# Untitled.net
KiCad netlist of a schematic drawn in EAGLE
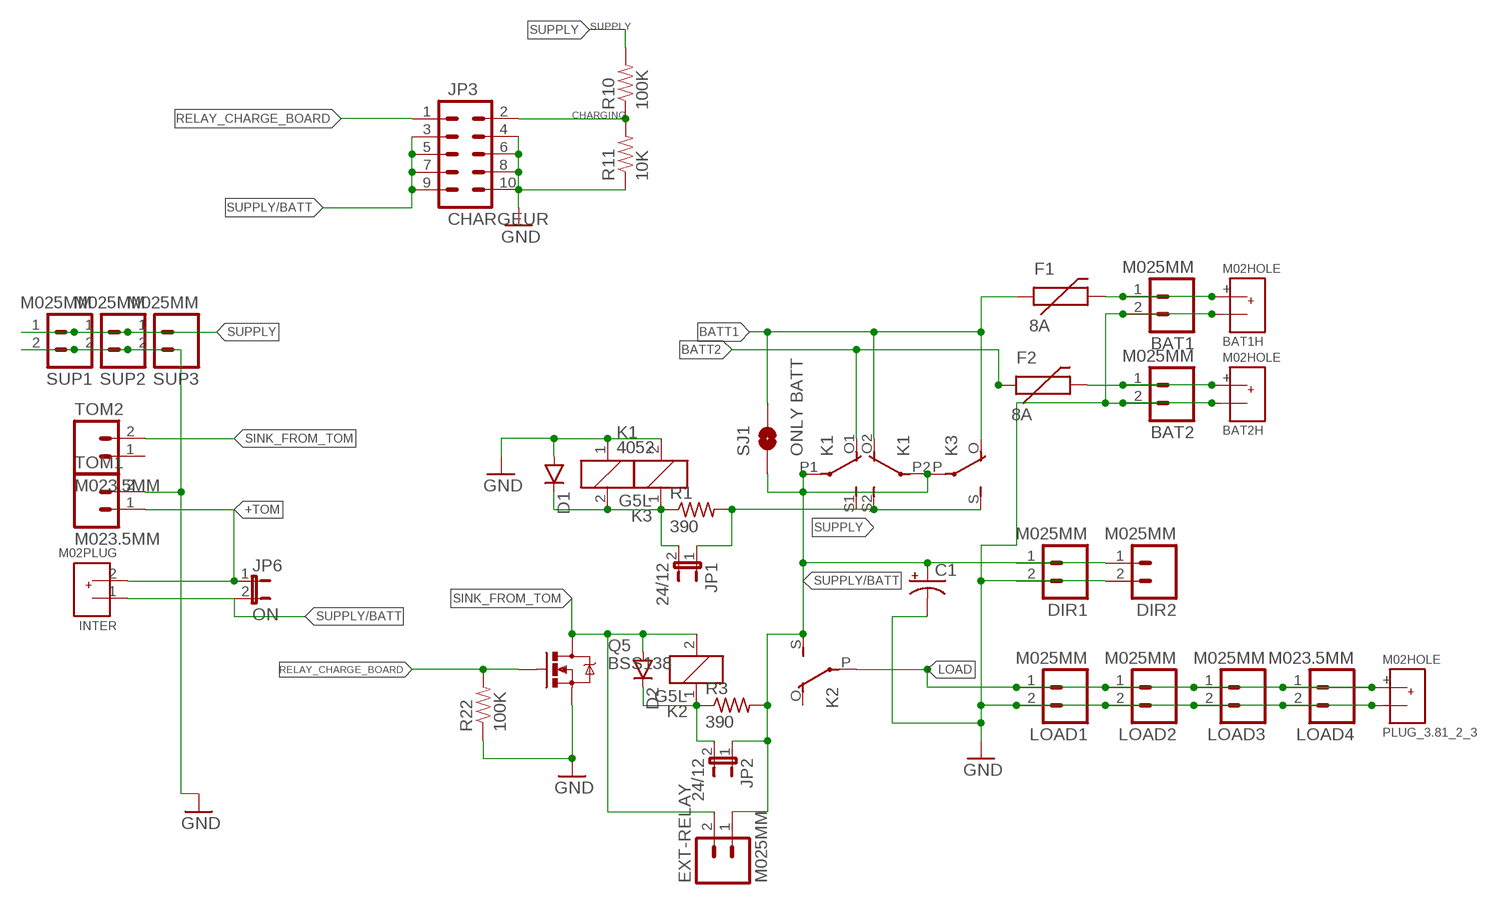
[diagram p0: schematic, sheet 1]

(export (version "E")
  (design (tool "Eeschema 10.0.6"))
  (components
    (comp (ref "BAT1")
      (value "M025MM")
      (footprint "eagle-import:SCREWTERMINAL-5MM-2")
      (libsource (lib "eagle-import") (part "M025MM"))
    )
    (comp (ref "BAT1H")
      (value "M02HOLE")
      (footprint "eagle-import:2X1_HOLE_BIG")
      (libsource (lib "eagle-import") (part "M02HOLE"))
    )
    (comp (ref "BAT2")
      (value "M025MM")
      (footprint "eagle-import:SCREWTERMINAL-5MM-2")
      (libsource (lib "eagle-import") (part "M025MM"))
    )
    (comp (ref "BAT2H")
      (value "M02HOLE")
      (footprint "eagle-import:2X1_HOLE_BIG")
      (libsource (lib "eagle-import") (part "M02HOLE"))
    )
    (comp (ref "C1")
      (value "CPOL-USSANYO_9F")
      (footprint "eagle-import:SANYO-OSCON_9F")
      (libsource (lib "eagle-import") (part "CPOL-USSANYO_9F"))
    )
    (comp (ref "D1")
      (value "DIODESMA-ALT")
      (footprint "eagle-import:SMA-DIODE_ALT")
      (libsource (lib "eagle-import") (part "DIODESMA-ALT"))
    )
    (comp (ref "D2")
      (value "DIODESMA-ALT")
      (footprint "eagle-import:SMA-DIODE_ALT")
      (libsource (lib "eagle-import") (part "DIODESMA-ALT"))
    )
    (comp (ref "DIR1")
      (value "M025MM")
      (footprint "eagle-import:SCREWTERMINAL-5MM-2")
      (libsource (lib "eagle-import") (part "M025MM"))
    )
    (comp (ref "DIR2")
      (value "M025MM")
      (footprint "eagle-import:SCREWTERMINAL-5MM-2")
      (libsource (lib "eagle-import") (part "M025MM"))
    )
    (comp (ref "EXT-RELAY")
      (value "M025MM")
      (footprint "eagle-import:SCREWTERMINAL-5MM-2")
      (libsource (lib "eagle-import") (part "M025MM"))
    )
    (comp (ref "F1")
      (value "8A")
      (footprint "eagle-import:PTC")
      (libsource (lib "eagle-import") (part "PTCPTH"))
    )
    (comp (ref "F2")
      (value "8A")
      (footprint "eagle-import:PTC")
      (libsource (lib "eagle-import") (part "PTCPTH"))
    )
    (comp (ref "INTER")
      (value "M02PLUG")
      (footprint "eagle-import:PLUG_02")
      (libsource (lib "eagle-import") (part "M02PLUG"))
    )
    (comp (ref "JP1")
      (value "24/12")
      (footprint "eagle-import:1X02_LOCK")
      (libsource (lib "eagle-import") (part "JUMPER-2PTH_LOCK"))
    )
    (comp (ref "JP2")
      (value "24/12")
      (footprint "eagle-import:1X02_LOCK")
      (libsource (lib "eagle-import") (part "JUMPER-2PTH_LOCK"))
    )
    (comp (ref "JP3")
      (value "CHARGEUR")
      (footprint "eagle-import:2X5_LOCK")
      (libsource (lib "eagle-import") (part "M05X2"))
    )
    (comp (ref "JP6")
      (value "ON")
      (footprint "eagle-import:1X02_LOCK")
      (libsource (lib "eagle-import") (part "JUMPER-2PTH_LOCK"))
    )
    (comp (ref "K1")
      (value "4052")
      (footprint "eagle-import:F4052")
      (fields (field (name "OC_FARNELL") "1169304"))
      (libsource (lib "eagle-import") (part "4052"))
    )
    (comp (ref "K2")
      (value "G5L")
      (footprint "eagle-import:G5LE")
      (libsource (lib "eagle-import") (part "G5L"))
    )
    (comp (ref "K3")
      (value "G5L")
      (footprint "eagle-import:G5LE")
      (fields (field (name "OC_FARNELL") "1455504"))
      (libsource (lib "eagle-import") (part "G5L"))
    )
    (comp (ref "LOAD1")
      (value "M025MM")
      (footprint "eagle-import:SCREWTERMINAL-5MM-2")
      (libsource (lib "eagle-import") (part "M025MM"))
    )
    (comp (ref "LOAD2")
      (value "M025MM")
      (footprint "eagle-import:SCREWTERMINAL-5MM-2")
      (libsource (lib "eagle-import") (part "M025MM"))
    )
    (comp (ref "LOAD3")
      (value "M025MM")
      (footprint "eagle-import:SCREWTERMINAL-5MM-2")
      (libsource (lib "eagle-import") (part "M025MM"))
    )
    (comp (ref "LOAD4")
      (value "M023.5MM")
      (footprint "eagle-import:SCREWTERMINAL-3.5MM-2")
      (libsource (lib "eagle-import") (part "M023.5MM"))
    )
    (comp (ref "PLUG_3.81_2_3")
      (value "M02HOLE")
      (footprint "eagle-import:2X1_HOLE_BIG")
      (libsource (lib "eagle-import") (part "M02HOLE"))
    )
    (comp (ref "Q5")
      (value "BSS138")
      (footprint "eagle-import:SOT23-3")
      (libsource (lib "eagle-import") (part "MOSFET-NCHANNELBSS138"))
    )
    (comp (ref "R1")
      (value "390")
      (footprint "eagle-import:R2512")
      (libsource (lib "eagle-import") (part "R-US_R2512"))
    )
    (comp (ref "R3")
      (value "390")
      (footprint "eagle-import:R2512")
      (libsource (lib "eagle-import") (part "R-US_R2512"))
    )
    (comp (ref "R10")
      (value "100K")
      (footprint "eagle-import:0603-RES")
      (libsource (lib "eagle-import") (part "RESISTOR0603-RES"))
    )
    (comp (ref "R11")
      (value "10K")
      (footprint "eagle-import:0603-RES")
      (libsource (lib "eagle-import") (part "RESISTOR0603-RES"))
    )
    (comp (ref "R22")
      (value "100K")
      (footprint "eagle-import:0603-RES")
      (libsource (lib "eagle-import") (part "RESISTOR0603-RES"))
    )
    (comp (ref "SJ1")
      (value "ONLY BATT")
      (footprint "eagle-import:SJ_2S-NO")
      (libsource (lib "eagle-import") (part "SOLDERJUMPERNO"))
    )
    (comp (ref "SUP1")
      (value "M025MM")
      (footprint "eagle-import:SCREWTERMINAL-5MM-2")
      (libsource (lib "eagle-import") (part "M025MM"))
    )
    (comp (ref "SUP2")
      (value "M025MM")
      (footprint "eagle-import:SCREWTERMINAL-5MM-2")
      (libsource (lib "eagle-import") (part "M025MM"))
    )
    (comp (ref "SUP3")
      (value "M025MM")
      (footprint "eagle-import:SCREWTERMINAL-5MM-2")
      (libsource (lib "eagle-import") (part "M025MM"))
    )
    (comp (ref "TOM1")
      (value "M023.5MM")
      (footprint "eagle-import:SCREWTERMINAL-3.5MM-2")
      (libsource (lib "eagle-import") (part "M023.5MM"))
    )
    (comp (ref "TOM2")
      (value "M023.5MM")
      (footprint "eagle-import:SCREWTERMINAL-3.5MM-2")
      (libsource (lib "eagle-import") (part "M023.5MM"))
    )
  )
  (nets
    (net (code "1") (name "+TOM") (class "Default")
      (node (ref "INTER") (pin "2") (pinfunction "2_2") (pintype "bidirectional"))
      (node (ref "JP6") (pin "1") (pinfunction "1_1") (pintype "passive"))
      (node (ref "TOM1") (pin "1") (pinfunction "1_1") (pintype "passive"))
    )
    (net (code "2") (name "/CHARGING") (class "Default")
      (node (ref "JP3") (pin "2") (pinfunction "2_2") (pintype "passive"))
      (node (ref "R10") (pin "1") (pinfunction "1_1") (pintype "passive"))
      (node (ref "R11") (pin "2") (pinfunction "2_2") (pintype "passive"))
    )
    (net (code "3") (name "BATT1") (class "Default")
      (node (ref "F1") (pin "P$1MOV") (pinfunction "1_P$1MOV") (pintype "bidirectional"))
      (node (ref "K1") (pin "O2") (pinfunction "O_O2") (pintype "passive"))
      (node (ref "K3") (pin "O") (pinfunction "O_O") (pintype "passive"))
      (node (ref "SJ1") (pin "2") (pinfunction "2_2") (pintype "passive"))
    )
    (net (code "4") (name "BATT2") (class "Default")
      (node (ref "F2") (pin "P$1MOV") (pinfunction "1_P$1MOV") (pintype "bidirectional"))
      (node (ref "K1") (pin "O1") (pinfunction "O_O1") (pintype "passive"))
    )
    (net (code "5") (name "GND") (class "Default")
      (node (ref "BAT1") (pin "2") (pinfunction "2_2") (pintype "passive"))
      (node (ref "BAT1H") (pin "_") (pinfunction "1__") (pintype "bidirectional"))
      (node (ref "BAT2") (pin "2") (pinfunction "2_2") (pintype "passive"))
      (node (ref "BAT2H") (pin "_") (pinfunction "1__") (pintype "bidirectional"))
      (node (ref "C1") (pin "-") (pinfunction "-_-") (pintype "passive"))
      (node (ref "D1") (pin "A") (pinfunction "A_A") (pintype "passive"))
      (node (ref "DIR1") (pin "2") (pinfunction "2_2") (pintype "passive"))
      (node (ref "DIR2") (pin "2") (pinfunction "2_2") (pintype "passive"))
      (node (ref "JP3") (pin "10") (pinfunction "10_10") (pintype "passive"))
      (node (ref "JP3") (pin "4") (pinfunction "4_4") (pintype "passive"))
      (node (ref "JP3") (pin "6") (pinfunction "6_6") (pintype "passive"))
      (node (ref "JP3") (pin "8") (pinfunction "8_8") (pintype "passive"))
      (node (ref "K1") (pin "1") (pinfunction "1_1") (pintype "passive"))
      (node (ref "K3") (pin "2") (pinfunction "2_2") (pintype "passive"))
      (node (ref "LOAD1") (pin "2") (pinfunction "2_2") (pintype "passive"))
      (node (ref "LOAD2") (pin "2") (pinfunction "2_2") (pintype "passive"))
      (node (ref "LOAD3") (pin "2") (pinfunction "2_2") (pintype "passive"))
      (node (ref "LOAD4") (pin "2") (pinfunction "2_2") (pintype "passive"))
      (node (ref "PLUG_3.81_2_3") (pin "_") (pinfunction "1__") (pintype "bidirectional"))
      (node (ref "Q5") (pin "2") (pinfunction "S_2") (pintype "passive"))
      (node (ref "R11") (pin "1") (pinfunction "1_1") (pintype "passive"))
      (node (ref "R22") (pin "1") (pinfunction "1_1") (pintype "passive"))
      (node (ref "SUP1") (pin "2") (pinfunction "2_2") (pintype "passive"))
      (node (ref "SUP2") (pin "2") (pinfunction "2_2") (pintype "passive"))
      (node (ref "SUP3") (pin "2") (pinfunction "2_2") (pintype "passive"))
      (node (ref "TOM1") (pin "2") (pinfunction "2_2") (pintype "passive"))
    )
    (net (code "6") (name "LOAD") (class "Default")
      (node (ref "K2") (pin "P") (pinfunction "P_P") (pintype "passive"))
      (node (ref "LOAD1") (pin "1") (pinfunction "1_1") (pintype "passive"))
      (node (ref "LOAD2") (pin "1") (pinfunction "1_1") (pintype "passive"))
      (node (ref "LOAD3") (pin "1") (pinfunction "1_1") (pintype "passive"))
      (node (ref "LOAD4") (pin "1") (pinfunction "1_1") (pintype "passive"))
      (node (ref "PLUG_3.81_2_3") (pin "+") (pinfunction "2_+") (pintype "bidirectional"))
    )
    (net (code "7") (name "Net-(BAT1H-2)") (class "Default")
      (node (ref "BAT1") (pin "1") (pinfunction "1_1") (pintype "passive"))
      (node (ref "BAT1H") (pin "+") (pinfunction "2_+") (pintype "bidirectional"))
      (node (ref "F1") (pin "P$2") (pinfunction "2_P$2") (pintype "bidirectional"))
    )
    (net (code "8") (name "Net-(BAT2H-2)") (class "Default")
      (node (ref "BAT2") (pin "1") (pinfunction "1_1") (pintype "passive"))
      (node (ref "BAT2H") (pin "+") (pinfunction "2_+") (pintype "bidirectional"))
      (node (ref "F2") (pin "P$2") (pinfunction "2_P$2") (pintype "bidirectional"))
    )
    (net (code "9") (name "Net-(D1-PadC)") (class "Default")
      (node (ref "D1") (pin "C") (pinfunction "C_C") (pintype "passive"))
      (node (ref "JP1") (pin "2") (pinfunction "2_2") (pintype "passive"))
      (node (ref "K1") (pin "2") (pinfunction "2_2") (pintype "passive"))
      (node (ref "K3") (pin "1") (pinfunction "1_1") (pintype "passive"))
      (node (ref "R1") (pin "1") (pinfunction "1_1") (pintype "passive"))
    )
    (net (code "10") (name "Net-(D2-PadC)") (class "Default")
      (node (ref "D2") (pin "C") (pinfunction "C_C") (pintype "passive"))
      (node (ref "JP2") (pin "2") (pinfunction "2_2") (pintype "passive"))
      (node (ref "K2") (pin "1") (pinfunction "1_1") (pintype "passive"))
      (node (ref "R3") (pin "1") (pinfunction "1_1") (pintype "passive"))
    )
    (net (code "11") (name "RELAY_CHARGE_BOARD") (class "Default")
      (node (ref "JP3") (pin "1") (pinfunction "1_1") (pintype "passive"))
      (node (ref "Q5") (pin "1") (pinfunction "G_1") (pintype "passive"))
      (node (ref "R22") (pin "2") (pinfunction "2_2") (pintype "passive"))
    )
    (net (code "12") (name "SINK_FROM_TOM") (class "Default")
      (node (ref "D2") (pin "A") (pinfunction "A_A") (pintype "passive"))
      (node (ref "EXT-RELAY") (pin "2") (pinfunction "2_2") (pintype "passive"))
      (node (ref "K2") (pin "2") (pinfunction "2_2") (pintype "passive"))
      (node (ref "Q5") (pin "3") (pinfunction "D_3") (pintype "passive"))
      (node (ref "TOM2") (pin "2") (pinfunction "2_2") (pintype "passive"))
    )
    (net (code "13") (name "SUPPLY") (class "Default")
      (node (ref "JP1") (pin "1") (pinfunction "1_1") (pintype "passive"))
      (node (ref "K1") (pin "S1") (pinfunction "S_S1") (pintype "passive"))
      (node (ref "K1") (pin "S2") (pinfunction "S_S2") (pintype "passive"))
      (node (ref "K3") (pin "S") (pinfunction "S_S") (pintype "passive"))
      (node (ref "R1") (pin "2") (pinfunction "2_2") (pintype "passive"))
      (node (ref "R10") (pin "2") (pinfunction "2_2") (pintype "passive"))
      (node (ref "SUP1") (pin "1") (pinfunction "1_1") (pintype "passive"))
      (node (ref "SUP2") (pin "1") (pinfunction "1_1") (pintype "passive"))
      (node (ref "SUP3") (pin "1") (pinfunction "1_1") (pintype "passive"))
    )
    (net (code "14") (name "SUPPLY{slash}BATT") (class "Default")
      (node (ref "C1") (pin "+") (pinfunction "+_+") (pintype "passive"))
      (node (ref "DIR1") (pin "1") (pinfunction "1_1") (pintype "passive"))
      (node (ref "DIR2") (pin "1") (pinfunction "1_1") (pintype "passive"))
      (node (ref "EXT-RELAY") (pin "1") (pinfunction "1_1") (pintype "passive"))
      (node (ref "INTER") (pin "1") (pinfunction "1_1") (pintype "bidirectional"))
      (node (ref "JP2") (pin "1") (pinfunction "1_1") (pintype "passive"))
      (node (ref "JP3") (pin "3") (pinfunction "3_3") (pintype "passive"))
      (node (ref "JP3") (pin "5") (pinfunction "5_5") (pintype "passive"))
      (node (ref "JP3") (pin "7") (pinfunction "7_7") (pintype "passive"))
      (node (ref "JP3") (pin "9") (pinfunction "9_9") (pintype "passive"))
      (node (ref "JP6") (pin "2") (pinfunction "2_2") (pintype "passive"))
      (node (ref "K1") (pin "P1") (pinfunction "P_P1") (pintype "passive"))
      (node (ref "K1") (pin "P2") (pinfunction "P_P2") (pintype "passive"))
      (node (ref "K2") (pin "S") (pinfunction "S_S") (pintype "passive"))
      (node (ref "K3") (pin "P") (pinfunction "P_P") (pintype "passive"))
      (node (ref "R3") (pin "2") (pinfunction "2_2") (pintype "passive"))
      (node (ref "SJ1") (pin "1") (pinfunction "1_1") (pintype "passive"))
    )
    (net (code "15") (name "unconnected-(K2-PadO)") (class "Default")
      (node (ref "K2") (pin "O") (pinfunction "O_O") (pintype "passive"))
    )
    (net (code "16") (name "unconnected-(TOM2-Pad1)") (class "Default")
      (node (ref "TOM2") (pin "1") (pinfunction "1_1") (pintype "passive"))
    )
  )
)
